# schematic_force_sensitive_resistor_drive.net
KiCad netlist of a schematic drawn in EAGLE
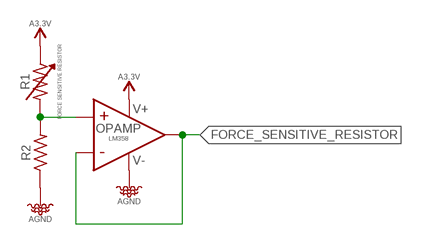
[diagram p0: schematic, sheet 1]

(export (version "E")
  (design (tool "Eeschema 10.0.6"))
  (components
    (comp (ref "OPAMP")
      (value "OPAMP_ILLUSTRATIVE")
      (footprint "eagle-import:SOT95P280X145-5")
      (libsource (lib "eagle-import") (part "OPAMP_ILLUSTRATIVE"))
    )
    (comp (ref "R1")
      (value "FORCE SENSITIVE RESISTOR")
      (footprint "eagle-import:PTH-CONNECTOR-2PIN")
      (fields
        (field (name "MFR") "TT Electronics/BI")
        (field (name "MPN") "P160KN2-0QA25B10K")
        (field (name "CREATOR") "MrSwirlyEyes")
      )
      (libsource (lib "eagle-import") (part "VARIABLE_PTH_10K-1/5W-20%_ACTLEN-25_OFFBOARD"))
    )
    (comp (ref "R2")
      (value "10K")
      (footprint "eagle-import:RESC1005X35_SMD-0402")
      (fields (field (name "MFR") "Yageo") (field (name "MPN") "RC0402JR-0710KP"))
      (libsource (lib "eagle-import") (part "10KΩ_SMD-0402_1/16W-5%"))
    )
  )
  (nets
    (net (code "1") (name "A3.3V") (class "Default")
      (node (ref "OPAMP") (pin "4") (pinfunction "V+_4") (pintype "passive"))
      (node (ref "R1") (pin "1") (pinfunction "1_1") (pintype "passive"))
    )
    (net (code "2") (name "AGND") (class "Default")
      (node (ref "OPAMP") (pin "5") (pinfunction "V-_5") (pintype "passive"))
      (node (ref "R2") (pin "1") (pinfunction "1_1") (pintype "passive"))
    )
    (net (code "3") (name "FORCE_SENSITIVE_RESISTOR") (class "Default")
      (node (ref "OPAMP") (pin "2") (pinfunction "IN-_2") (pintype "input"))
      (node (ref "OPAMP") (pin "3") (pinfunction "OUT_3") (pintype "output"))
    )
    (net (code "4") (name "Net-(OPAMP-IN+)") (class "Default")
      (node (ref "OPAMP") (pin "1") (pinfunction "IN+_1") (pintype "input"))
      (node (ref "R1") (pin "2") (pinfunction "2_2") (pintype "passive"))
      (node (ref "R2") (pin "2") (pinfunction "2_2") (pintype "passive"))
    )
  )
)
